# Adafruit_Infineon_Trust_M.net
KiCad netlist of a schematic drawn in EAGLE
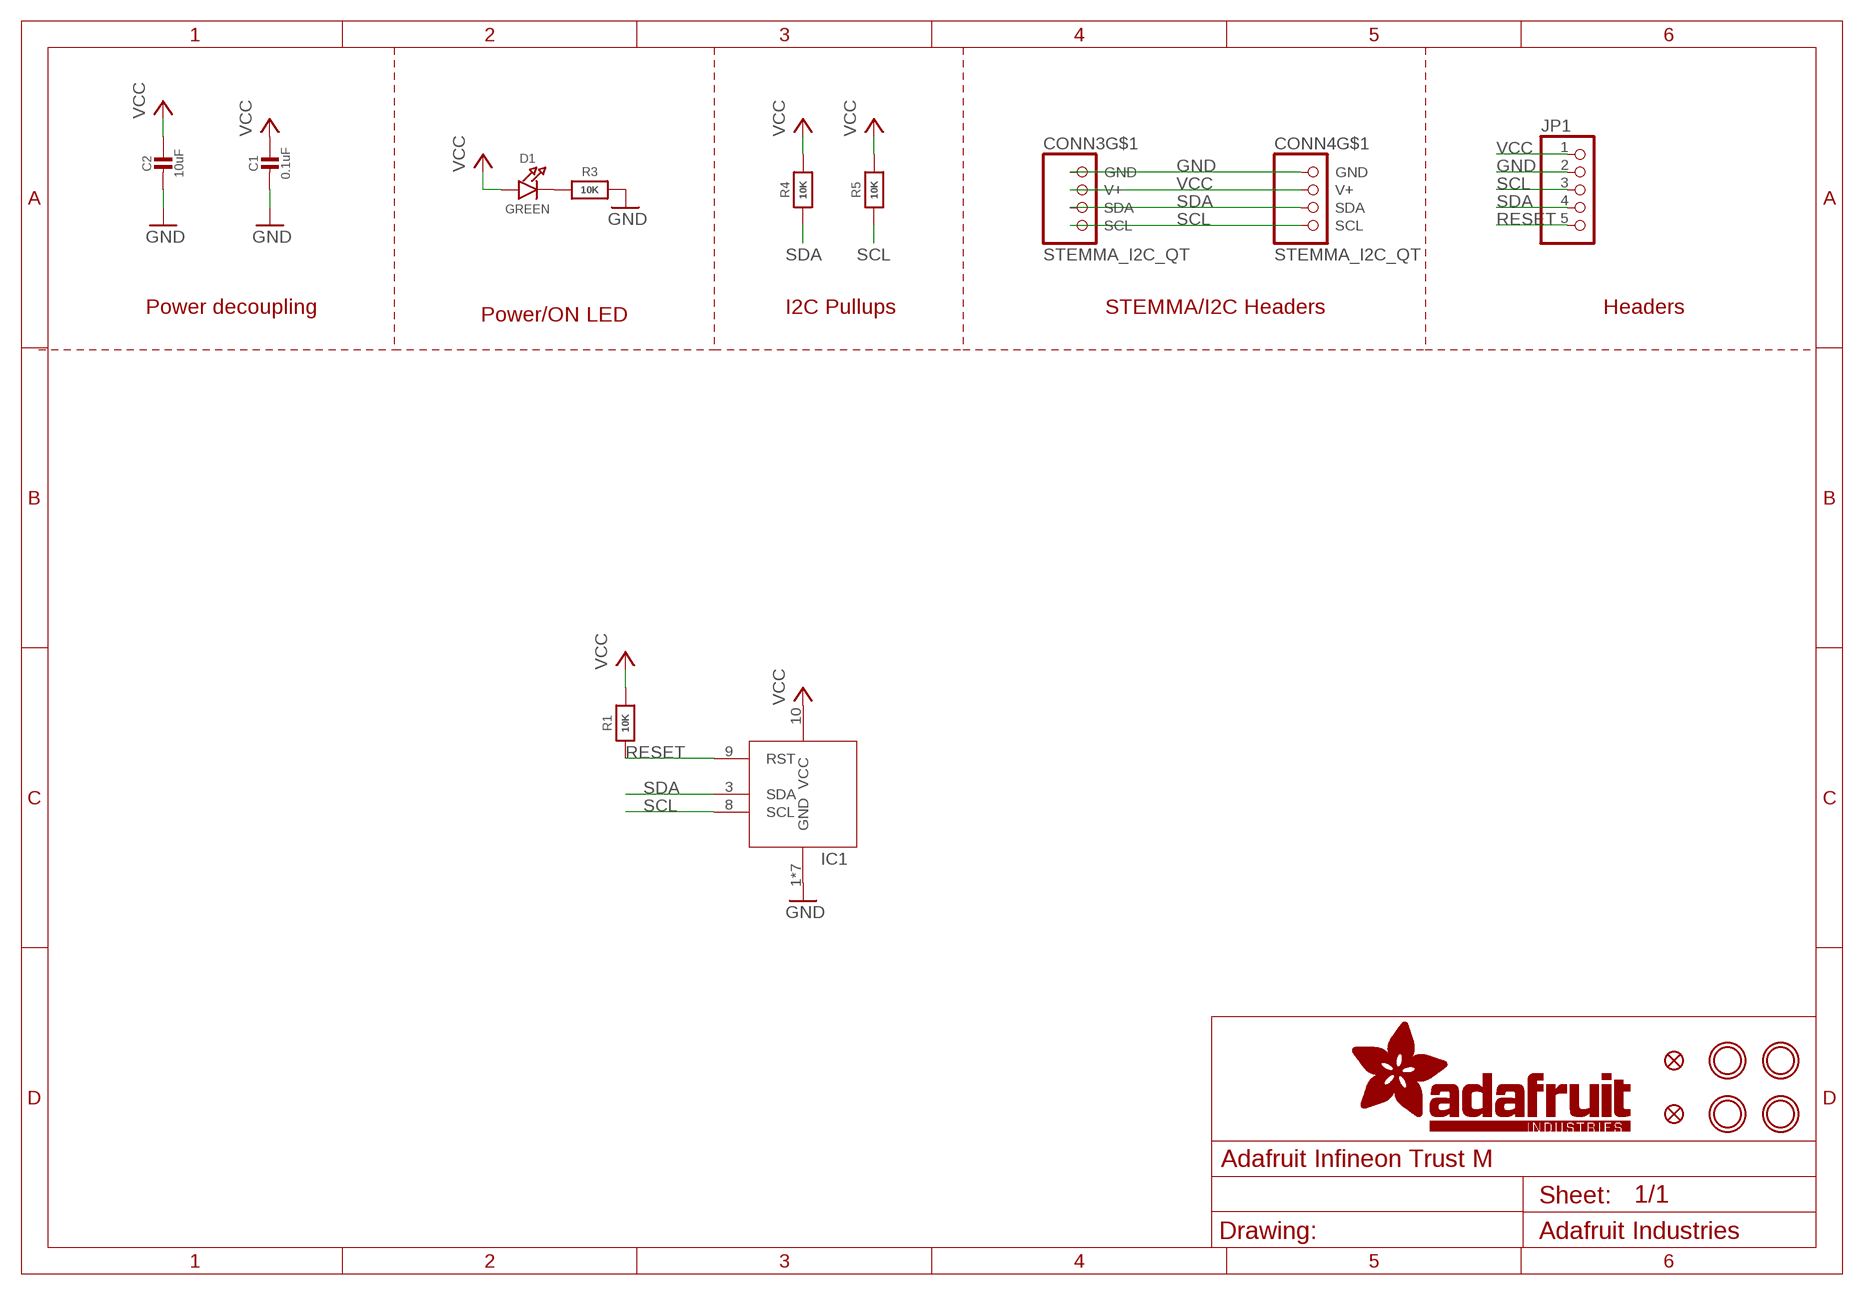
[diagram p0: schematic, sheet 1]

(export (version "E")
  (design (tool "Eeschema 10.0.6"))
  (components
    (comp (ref "C1")
      (value "0.1uF")
      (footprint "eagle-import:0603-NO")
      (libsource (lib "eagle-import") (part "CAP_CERAMIC0603_NO"))
    )
    (comp (ref "C2")
      (value "10uF")
      (footprint "eagle-import:0805-NO")
      (libsource (lib "eagle-import") (part "CAP_CERAMIC0805-NOOUTLINE"))
    )
    (comp (ref "CONN3")
      (value "STEMMA_I2C_QT")
      (footprint "eagle-import:JST_SH4")
      (libsource (lib "eagle-import") (part "STEMMA_I2C_QT"))
    )
    (comp (ref "CONN4")
      (value "STEMMA_I2C_QT")
      (footprint "eagle-import:JST_SH4")
      (libsource (lib "eagle-import") (part "STEMMA_I2C_QT"))
    )
    (comp (ref "D1")
      (value "GREEN")
      (footprint "eagle-import:CHIPLED_0603_NOOUTLINE")
      (libsource (lib "eagle-import") (part "LED0603_NOOUTLINE"))
    )
    (comp (ref "FID3")
      (value "FIDUCIAL_1MM")
      (footprint "eagle-import:FIDUCIAL_1MM")
      (libsource (lib "eagle-import") (part "FIDUCIAL_1MM"))
    )
    (comp (ref "FID4")
      (value "FIDUCIAL_1MM")
      (footprint "eagle-import:FIDUCIAL_1MM")
      (libsource (lib "eagle-import") (part "FIDUCIAL_1MM"))
    )
    (comp (ref "IC1")
      (value "OPTIGA_TRUST_X")
      (footprint "eagle-import:PG-USON10-10-2")
      (libsource (lib "eagle-import") (part "OPTIGA_TRUST_X"))
    )
    (comp (ref "JP1")
      (value "HEADER-1X570MIL")
      (footprint "eagle-import:1X05_ROUND_70")
      (libsource (lib "eagle-import") (part "HEADER-1X570MIL"))
    )
    (comp (ref "R1")
      (value "10K")
      (footprint "eagle-import:0603-NO")
      (libsource (lib "eagle-import") (part "RESISTOR_0603_NOOUT"))
    )
    (comp (ref "R3")
      (value "10K")
      (footprint "eagle-import:0603-NO")
      (libsource (lib "eagle-import") (part "RESISTOR_0603_NOOUT"))
    )
    (comp (ref "R4")
      (value "10K")
      (footprint "eagle-import:0603-NO")
      (libsource (lib "eagle-import") (part "RESISTOR_0603_NOOUT"))
    )
    (comp (ref "R5")
      (value "10K")
      (footprint "eagle-import:0603-NO")
      (libsource (lib "eagle-import") (part "RESISTOR_0603_NOOUT"))
    )
    (comp (ref "U$11")
      (value "MOUNTINGHOLE2.5")
      (footprint "eagle-import:MOUNTINGHOLE_2.5_PLATED")
      (libsource (lib "eagle-import") (part "MOUNTINGHOLE2.5"))
    )
    (comp (ref "U$12")
      (value "MOUNTINGHOLE2.5")
      (footprint "eagle-import:MOUNTINGHOLE_2.5_PLATED")
      (libsource (lib "eagle-import") (part "MOUNTINGHOLE2.5"))
    )
    (comp (ref "U$14")
      (value "MOUNTINGHOLE2.5")
      (footprint "eagle-import:MOUNTINGHOLE_2.5_PLATED")
      (libsource (lib "eagle-import") (part "MOUNTINGHOLE2.5"))
    )
    (comp (ref "U$15")
      (value "MOUNTINGHOLE2.5")
      (footprint "eagle-import:MOUNTINGHOLE_2.5_PLATED")
      (libsource (lib "eagle-import") (part "MOUNTINGHOLE2.5"))
    )
  )
  (nets
    (net (code "1") (name "/RESET") (class "Default")
      (node (ref "IC1") (pin "9") (pinfunction "RST_9") (pintype "input"))
      (node (ref "JP1") (pin "5") (pinfunction "5_5") (pintype "passive"))
      (node (ref "R1") (pin "1") (pinfunction "1_1") (pintype "passive"))
    )
    (net (code "2") (name "/SCL") (class "Default")
      (node (ref "CONN3") (pin "4") (pinfunction "SCL_4") (pintype "passive"))
      (node (ref "CONN4") (pin "4") (pinfunction "SCL_4") (pintype "passive"))
      (node (ref "IC1") (pin "8") (pinfunction "SCL_8") (pintype "bidirectional"))
      (node (ref "JP1") (pin "3") (pinfunction "3_3") (pintype "passive"))
      (node (ref "R5") (pin "1") (pinfunction "1_1") (pintype "passive"))
    )
    (net (code "3") (name "/SDA") (class "Default")
      (node (ref "CONN3") (pin "3") (pinfunction "SDA_3") (pintype "passive"))
      (node (ref "CONN4") (pin "3") (pinfunction "SDA_3") (pintype "passive"))
      (node (ref "IC1") (pin "3") (pinfunction "SDA_3") (pintype "bidirectional"))
      (node (ref "JP1") (pin "4") (pinfunction "4_4") (pintype "passive"))
      (node (ref "R4") (pin "1") (pinfunction "1_1") (pintype "passive"))
    )
    (net (code "4") (name "GND") (class "Default")
      (node (ref "C1") (pin "2") (pinfunction "2_2") (pintype "passive"))
      (node (ref "C2") (pin "2") (pinfunction "2_2") (pintype "passive"))
      (node (ref "CONN3") (pin "1") (pinfunction "GND_1") (pintype "passive"))
      (node (ref "CONN4") (pin "1") (pinfunction "GND_1") (pintype "passive"))
      (node (ref "IC1") (pin "1") (pinfunction "GND_1") (pintype "power_in"))
      (node (ref "IC1") (pin "2") (pinfunction "GND_2") (pintype "power_in"))
      (node (ref "IC1") (pin "4") (pinfunction "GND_4") (pintype "power_in"))
      (node (ref "IC1") (pin "5") (pinfunction "GND_5") (pintype "power_in"))
      (node (ref "IC1") (pin "6") (pinfunction "GND_6") (pintype "power_in"))
      (node (ref "IC1") (pin "7") (pinfunction "GND_7") (pintype "power_in"))
      (node (ref "IC1") (pin "THERM") (pinfunction "GND_THERM") (pintype "power_in"))
      (node (ref "JP1") (pin "2") (pinfunction "2_2") (pintype "passive"))
      (node (ref "R3") (pin "2") (pinfunction "2_2") (pintype "passive"))
    )
    (net (code "5") (name "Net-(D1-PadC)") (class "Default")
      (node (ref "D1") (pin "C") (pinfunction "C_C") (pintype "passive"))
      (node (ref "R3") (pin "1") (pinfunction "1_1") (pintype "passive"))
    )
    (net (code "6") (name "VCC") (class "Default")
      (node (ref "C1") (pin "1") (pinfunction "1_1") (pintype "passive"))
      (node (ref "C2") (pin "1") (pinfunction "1_1") (pintype "passive"))
      (node (ref "CONN3") (pin "2") (pinfunction "V+_2") (pintype "passive"))
      (node (ref "CONN4") (pin "2") (pinfunction "V+_2") (pintype "passive"))
      (node (ref "D1") (pin "A") (pinfunction "A_A") (pintype "passive"))
      (node (ref "IC1") (pin "10") (pinfunction "VCC_10") (pintype "power_in"))
      (node (ref "JP1") (pin "1") (pinfunction "1_1") (pintype "passive"))
      (node (ref "R1") (pin "2") (pinfunction "2_2") (pintype "passive"))
      (node (ref "R4") (pin "2") (pinfunction "2_2") (pintype "passive"))
      (node (ref "R5") (pin "2") (pinfunction "2_2") (pintype "passive"))
    )
  )
)
